# 12V6_Boost.net
KiCad netlist of a schematic drawn in Altium Designer
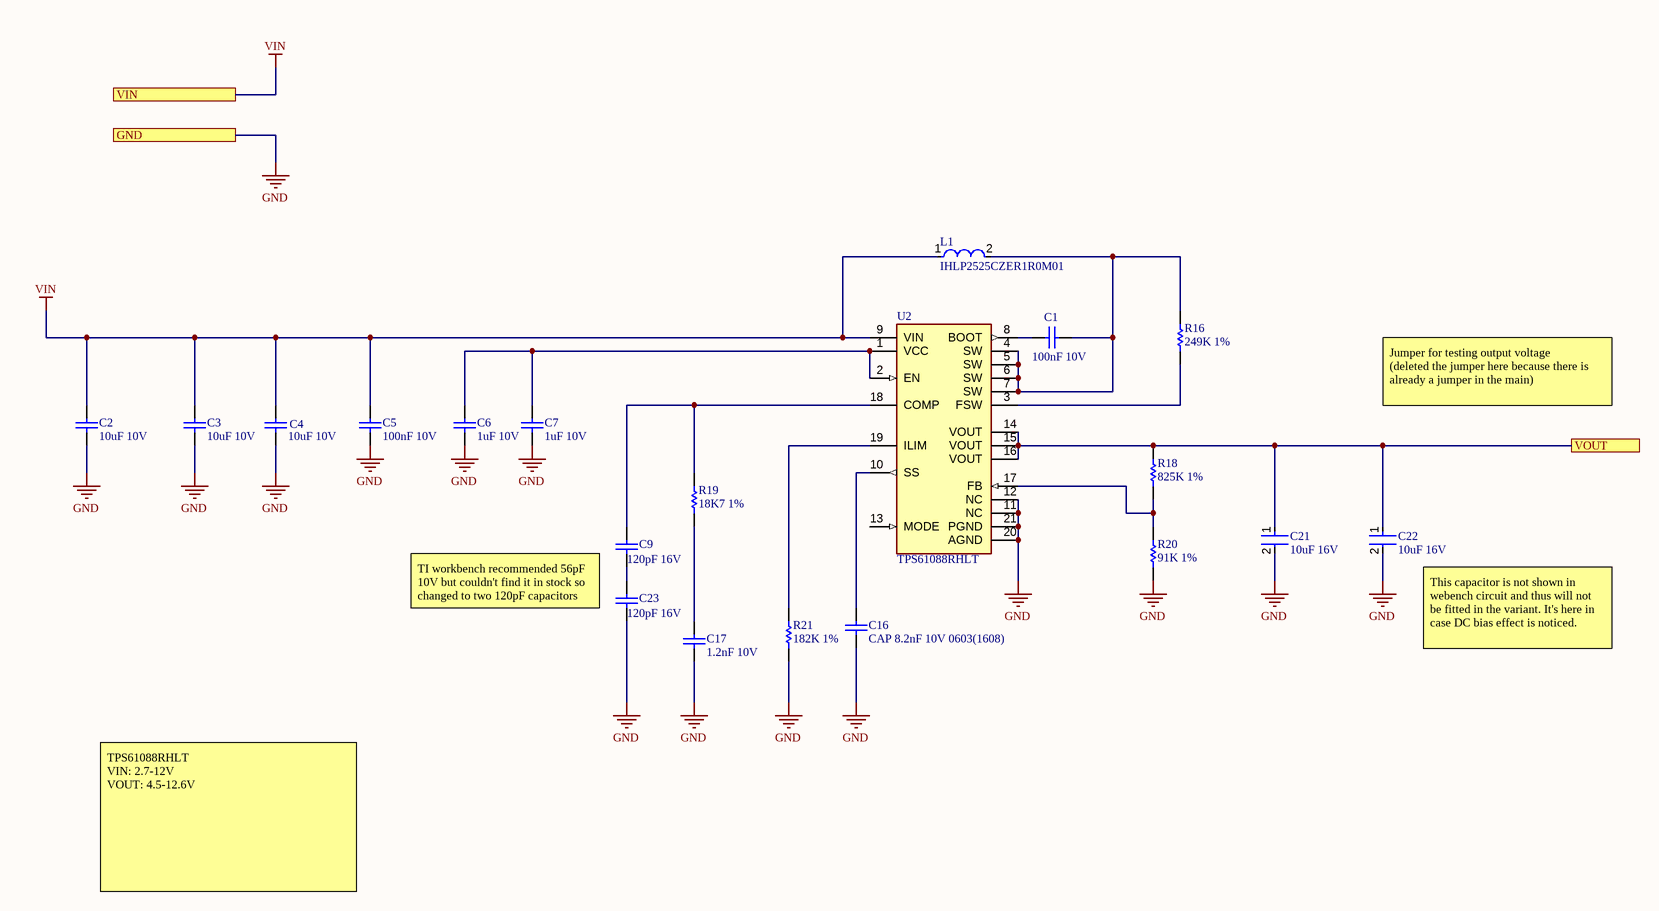
[diagram p0: 12V6_Boost.SchDoc]

(export (version "E")
  (design (tool "Eeschema 10.0.6"))
  (components
    (comp (ref "C1")
      (value "100nF 10V")
      (footprint "CAPC0603(1608)100_L")
      (description "CAP 100nF 10V ±5% 0603 (1608 Metric) Thickness 1mm SMD")
      (fields (field (name "TOLERANCE") "Â±5%"))
      (libsource (lib "Altium Content Vault") (part "CAP"))
    )
    (comp (ref "C2")
      (value "10uF 10V")
      (footprint "CAPC0603(1608)100_N")
      (description "CAP 10uF 10V ±10% 0603 (1608 Metric) Thickness 1mm SMD")
      (fields (field (name "TOLERANCE") "Â±10%"))
      (libsource (lib "Altium Content Vault") (part "CAP"))
    )
    (comp (ref "C3")
      (value "10uF 10V")
      (footprint "CAPC0603(1608)100_N")
      (description "CAP 10uF 10V ±10% 0603 (1608 Metric) Thickness 1mm SMD")
      (fields (field (name "TOLERANCE") "Â±10%"))
      (libsource (lib "Altium Content Vault") (part "CAP"))
    )
    (comp (ref "C4")
      (value "10uF 10V")
      (footprint "CAPC0603(1608)100_N")
      (description "CAP 10uF 10V ±10% 0603 (1608 Metric) Thickness 1mm SMD")
      (fields (field (name "TOLERANCE") "Â±10%"))
      (libsource (lib "Altium Content Vault") (part "CAP"))
    )
    (comp (ref "C5")
      (value "100nF 10V")
      (footprint "CAPC0603(1608)100_L")
      (fields (field (name "TOLERANCE") "Â±5%"))
      (libsource (lib "Altium Content Vault") (part "CAP"))
    )
    (comp (ref "C6")
      (value "1uF 10V")
      (footprint "CAPC0603(1608)100_M")
      (description "CAP 1uF 10V ±10% 0603 (1608 Metric) Thickness 1mm SMD")
      (fields (field (name "TOLERANCE") "Â±10%"))
      (libsource (lib "Altium Content Vault") (part "CAP"))
    )
    (comp (ref "C7")
      (value "1uF 10V")
      (footprint "CAPC0603(1608)100_M")
      (description "CAP 1uF 10V ±10% 0603 (1608 Metric) Thickness 1mm SMD")
      (fields (field (name "TOLERANCE") "Â±10%"))
      (libsource (lib "Altium Content Vault") (part "CAP"))
    )
    (comp (ref "C9")
      (value "120pF 16V")
      (footprint "CAPC0402(1005)60_N")
      (description "CAP 120pF 16V ±1% 0402 (1005 Metric) Thickness 0.6mm SMD")
      (fields (field (name "TOLERANCE") "Â±1%"))
      (libsource (lib "Altium Content Vault") (part "CAP"))
    )
    (comp (ref "C16")
      (value "CAP 8.2nF 10V 0603(1608)")
      (footprint "CAPC0603(1608)100_N")
      (description "CAP 8.2nF 10V ±5% 0603 (1608 Metric) Thickness 1mm SMD")
      (fields (field (name "TOLERANCE") "Â±5%"))
      (libsource (lib "Altium Content Vault") (part "CAP"))
    )
    (comp (ref "C17")
      (value "1.2nF 10V")
      (footprint "CAPC0603(1608)100_L")
      (description "CAP 1.2nF 10V ±1% 0603 (1608 Metric) Thickness 1mm SMD")
      (fields (field (name "TOLERANCE") "Â±1%"))
      (libsource (lib "Altium Content Vault") (part "CAP"))
    )
    (comp (ref "C21")
      (value "10uF 16V")
      (footprint "FP-CL21-IPC_B")
      (description "CL21 Series 0805 10uF 16V ±10% Tolerance X5R Multilayer Ceramic Chip Capacitor")
      (fields (field (name "TOLERANCE") "10%"))
      (libsource (lib "Altium Content Vault") (part "b4654b650e69147ec39a6b967a45e02"))
    )
    (comp (ref "C22")
      (value "10uF 16V")
      (footprint "FP-CL21-IPC_B")
      (description "CL21 Series 0805 10uF 16V ±10% Tolerance X5R Multilayer Ceramic Chip Capacitor")
      (fields (field (name "TOLERANCE") "10%"))
      (libsource (lib "Altium Content Vault") (part "b4654b650e69147ec39a6b967a45e02"))
    )
    (comp (ref "C23")
      (value "120pF 16V")
      (footprint "CAPC0402(1005)60_N")
      (description "CAP 120pF 16V ±1% 0402 (1005 Metric) Thickness 0.6mm SMD")
      (fields (field (name "TOLERANCE") "Â±1%"))
      (libsource (lib "Altium Content Vault") (part "CAP"))
    )
    (comp (ref "L1")
      (value "IHLP2525CZER1R0M01")
      (footprint "FP-IHLP-2525CZ-FP_2_413x3-MFG")
      (description "Commercial Inductors, High Saturation Series 1uH 11A 10mΩ 20%")
      (fields (field (name "TOLERANCE") "20%"))
      (libsource (lib "Altium Content Vault") (part "725321dda6339637d4d059423bc1c3c"))
    )
    (comp (ref "R16")
      (value "249K 1%")
      (footprint "RESC0603(1608)_L")
      (description "249K 0.1W 1% 0603 (1608 Metric)  SMD")
      (fields (field (name "POWER") "0.1 W") (field (name "TOLERANCE") "1 %"))
      (libsource (lib "Altium Content Vault") (part "RES"))
    )
    (comp (ref "R18")
      (value "825K 1%")
      (footprint "RESC0402(1005)_N")
      (description "825K 0.063W 1% 0402 (1005 Metric)  SMD")
      (fields (field (name "TOLERANCE") "1 %") (field (name "POWER") "0.063 W"))
      (libsource (lib "Altium Content Vault") (part "RES"))
    )
    (comp (ref "R19")
      (value "18K7 1%")
      (footprint "RESC0603(1608)_L")
      (description "18K7 0.1W 1% 0603 (1608 Metric)  SMD")
      (fields (field (name "POWER") "0.1 W") (field (name "TOLERANCE") "1 %"))
      (libsource (lib "Altium Content Vault") (part "RES"))
    )
    (comp (ref "R20")
      (value "91K 1%")
      (footprint "RESC0402(1005)_M")
      (description "91K 0.063W 1% 0402 (1005 Metric)  SMD")
      (fields (field (name "POWER") "0.063 W") (field (name "TOLERANCE") "1 %"))
      (libsource (lib "Altium Content Vault") (part "RES"))
    )
    (comp (ref "R21")
      (value "182K 1%")
      (footprint "RESC0603(1608)_L")
      (description "182K 0.1W 1% 0603 (1608 Metric)  SMD")
      (fields (field (name "POWER") "0.1 W") (field (name "TOLERANCE") "1 %"))
      (libsource (lib "Altium Content Vault") (part "RES"))
    )
    (comp (ref "U2")
      (value "TPS61088RHLT")
      (footprint "FP-RHL0020A-MFG")
      (description "IC REG BOOST ADJ 10A 20VQFN")
      (fields
        (field (name "OCTOPART") "https://octopart.com/tps61088rhlt-texas+instruments-57155059")
        (field (name "MANUFACTURER") "Texas Instruments")
      )
      (libsource (lib "Altium Content Vault") (part "866d791168d43c93e8e886550da2fd8"))
    )
  )
  (nets
    (net (code "1") (name "/VOUT") (class "Default")
      (node (ref "C21") (pin "1") (pinfunction "1_1") (pintype "passive"))
      (node (ref "C22") (pin "1") (pinfunction "1_1") (pintype "passive"))
      (node (ref "R18") (pin "2") (pinfunction "2_2") (pintype "passive"))
      (node (ref "U2") (pin "14") (pinfunction "VOUT_14") (pintype "power_in"))
      (node (ref "U2") (pin "15") (pinfunction "VOUT_15") (pintype "power_in"))
      (node (ref "U2") (pin "16") (pinfunction "VOUT_16") (pintype "power_in"))
    )
    (net (code "2") (name "GND") (class "Default")
      (node (ref "C16") (pin "2") (pinfunction "2_2") (pintype "passive"))
      (node (ref "C17") (pin "1") (pinfunction "1_1") (pintype "passive"))
      (node (ref "C2") (pin "1") (pinfunction "1_1") (pintype "passive"))
      (node (ref "C21") (pin "2") (pinfunction "2_2") (pintype "passive"))
      (node (ref "C22") (pin "2") (pinfunction "2_2") (pintype "passive"))
      (node (ref "C23") (pin "1") (pinfunction "1_1") (pintype "passive"))
      (node (ref "C3") (pin "1") (pinfunction "1_1") (pintype "passive"))
      (node (ref "C4") (pin "1") (pinfunction "1_1") (pintype "passive"))
      (node (ref "C5") (pin "1") (pinfunction "1_1") (pintype "passive"))
      (node (ref "C6") (pin "1") (pinfunction "1_1") (pintype "passive"))
      (node (ref "C7") (pin "1") (pinfunction "1_1") (pintype "passive"))
      (node (ref "R20") (pin "1") (pinfunction "1_1") (pintype "passive"))
      (node (ref "R21") (pin "1") (pinfunction "1_1") (pintype "passive"))
      (node (ref "U2") (pin "11") (pinfunction "NC_11") (pintype "passive"))
      (node (ref "U2") (pin "12") (pinfunction "NC_12") (pintype "passive"))
      (node (ref "U2") (pin "20") (pinfunction "AGND_20") (pintype "power_in"))
      (node (ref "U2") (pin "21") (pinfunction "PGND_21") (pintype "power_in"))
    )
    (net (code "3") (name "Net-(C1-Pad1)") (class "Default")
      (node (ref "C1") (pin "1") (pinfunction "1_1") (pintype "passive"))
      (node (ref "L1") (pin "2") (pinfunction "2_2") (pintype "passive"))
      (node (ref "R16") (pin "2") (pinfunction "2_2") (pintype "passive"))
      (node (ref "U2") (pin "4") (pinfunction "SW_4") (pintype "power_in"))
      (node (ref "U2") (pin "5") (pinfunction "SW_5") (pintype "power_in"))
      (node (ref "U2") (pin "6") (pinfunction "SW_6") (pintype "power_in"))
      (node (ref "U2") (pin "7") (pinfunction "SW_7") (pintype "power_in"))
    )
    (net (code "4") (name "Net-(C17-Pad2)") (class "Default")
      (node (ref "C17") (pin "2") (pinfunction "2_2") (pintype "passive"))
      (node (ref "R19") (pin "1") (pinfunction "1_1") (pintype "passive"))
    )
    (net (code "5") (name "Net-(C23-Pad2)") (class "Default")
      (node (ref "C23") (pin "2") (pinfunction "2_2") (pintype "passive"))
      (node (ref "C9") (pin "1") (pinfunction "1_1") (pintype "passive"))
    )
    (net (code "6") (name "Net-(U2-BOOT)") (class "Default")
      (node (ref "C1") (pin "2") (pinfunction "2_2") (pintype "passive"))
      (node (ref "U2") (pin "8") (pinfunction "BOOT_8") (pintype "output"))
    )
    (net (code "7") (name "Net-(U2-COMP)") (class "Default")
      (node (ref "C9") (pin "2") (pinfunction "2_2") (pintype "passive"))
      (node (ref "R19") (pin "2") (pinfunction "2_2") (pintype "passive"))
      (node (ref "U2") (pin "18") (pinfunction "COMP_18") (pintype "passive"))
    )
    (net (code "8") (name "Net-(U2-EN)") (class "Default")
      (node (ref "C6") (pin "2") (pinfunction "2_2") (pintype "passive"))
      (node (ref "C7") (pin "2") (pinfunction "2_2") (pintype "passive"))
      (node (ref "U2") (pin "1") (pinfunction "VCC_1") (pintype "power_in"))
      (node (ref "U2") (pin "2") (pinfunction "EN_2") (pintype "input"))
    )
    (net (code "9") (name "Net-(U2-FB)") (class "Default")
      (node (ref "R18") (pin "1") (pinfunction "1_1") (pintype "passive"))
      (node (ref "R20") (pin "2") (pinfunction "2_2") (pintype "passive"))
      (node (ref "U2") (pin "17") (pinfunction "FB_17") (pintype "input"))
    )
    (net (code "10") (name "Net-(U2-FSW)") (class "Default")
      (node (ref "R16") (pin "1") (pinfunction "1_1") (pintype "passive"))
      (node (ref "U2") (pin "3") (pinfunction "FSW_3") (pintype "passive"))
    )
    (net (code "11") (name "Net-(U2-ILIM)") (class "Default")
      (node (ref "R21") (pin "2") (pinfunction "2_2") (pintype "passive"))
      (node (ref "U2") (pin "19") (pinfunction "ILIM_19") (pintype "passive"))
    )
    (net (code "12") (name "Net-(U2-SS)") (class "Default")
      (node (ref "C16") (pin "1") (pinfunction "1_1") (pintype "passive"))
      (node (ref "U2") (pin "10") (pinfunction "SS_10") (pintype "output"))
    )
    (net (code "13") (name "VIN") (class "Default")
      (node (ref "C2") (pin "2") (pinfunction "2_2") (pintype "passive"))
      (node (ref "C3") (pin "2") (pinfunction "2_2") (pintype "passive"))
      (node (ref "C4") (pin "2") (pinfunction "2_2") (pintype "passive"))
      (node (ref "C5") (pin "2") (pinfunction "2_2") (pintype "passive"))
      (node (ref "L1") (pin "1") (pinfunction "1_1") (pintype "passive"))
      (node (ref "U2") (pin "9") (pinfunction "VIN_9") (pintype "power_in"))
    )
    (net (code "14") (name "unconnected-(U2-MODE-Pad13)") (class "Default")
      (node (ref "U2") (pin "13") (pinfunction "MODE_13") (pintype "input"))
    )
  )
)
